# compact.net
KiCad netlist of a schematic drawn in EAGLE
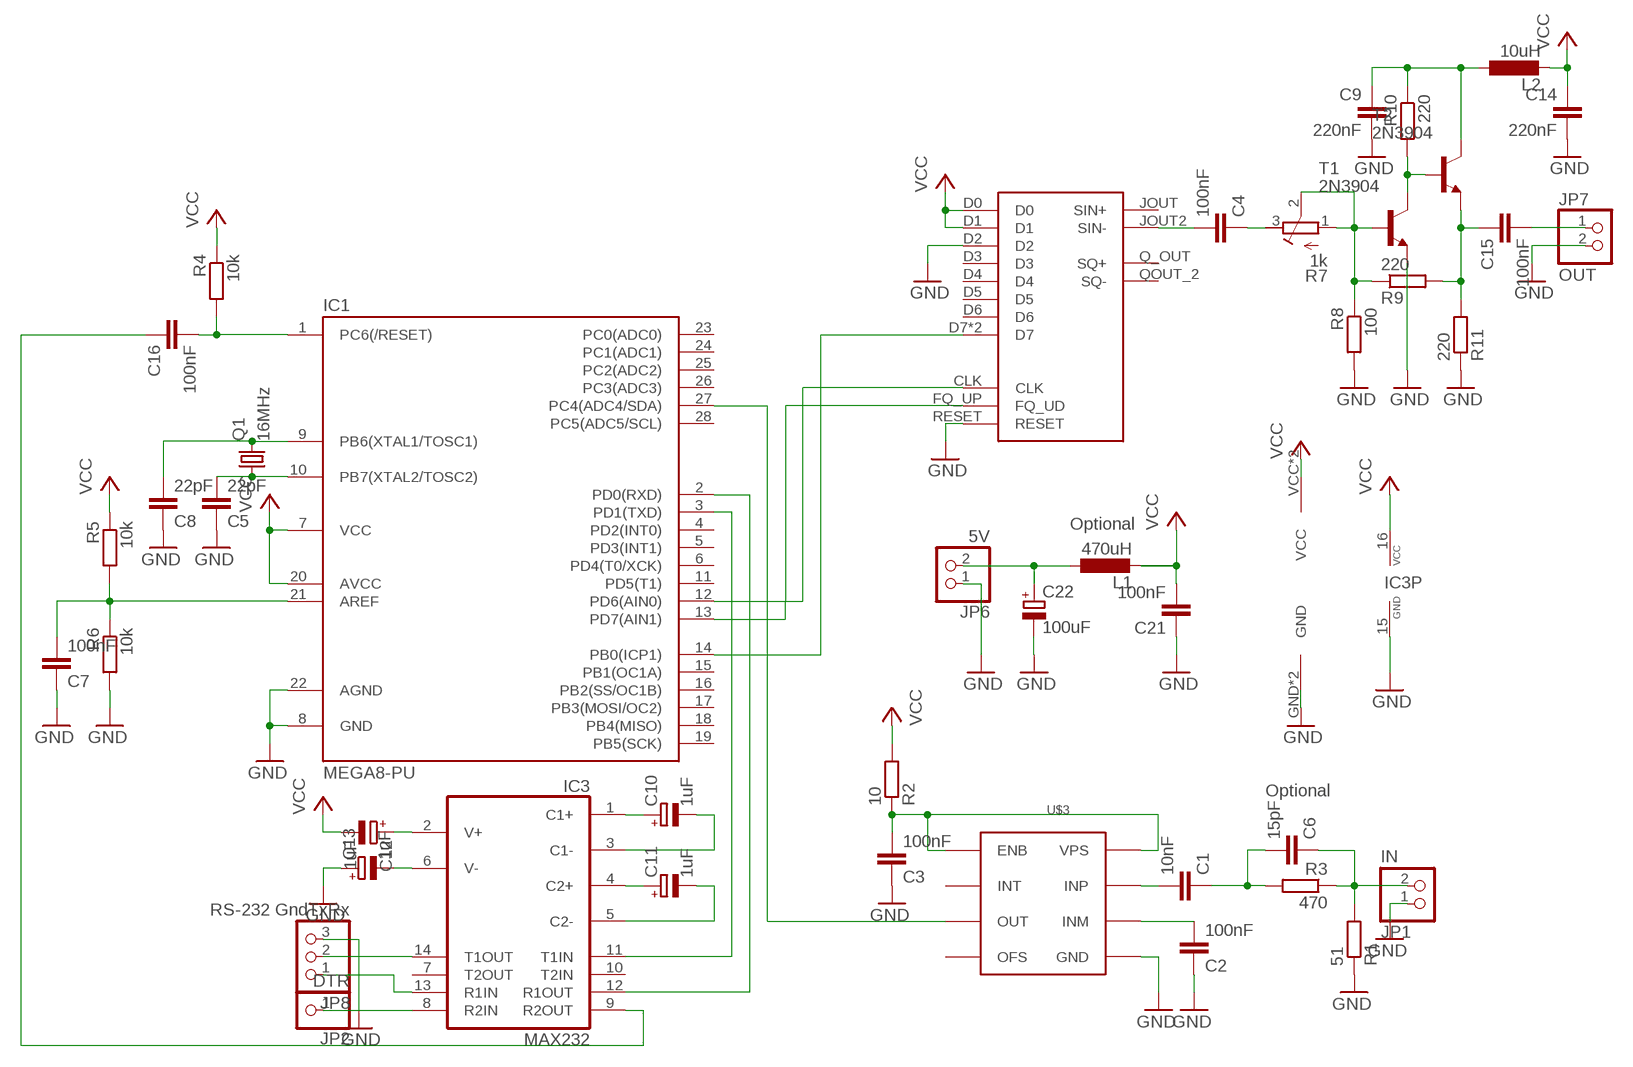
[diagram p0: schematic, sheet 1]

(export (version "E")
  (design (tool "Eeschema 10.0.6"))
  (components
    (comp (ref "C1")
      (value "10nF")
      (footprint "eagle-import:C050-025X075")
      (libsource (lib "eagle-import") (part "C-EU050-025X075"))
    )
    (comp (ref "C2")
      (value "100nF")
      (footprint "eagle-import:C025-025X050")
      (libsource (lib "eagle-import") (part "C-EU025-025X050"))
    )
    (comp (ref "C3")
      (value "100nF")
      (footprint "eagle-import:C025-025X050")
      (libsource (lib "eagle-import") (part "C-EU025-025X050"))
    )
    (comp (ref "C4")
      (value "100nF")
      (footprint "eagle-import:C025-025X050")
      (libsource (lib "eagle-import") (part "C-EU025-025X050"))
    )
    (comp (ref "C5")
      (value "22pF")
      (footprint "eagle-import:C102-043X133")
      (libsource (lib "eagle-import") (part "C-EU102-043X133"))
    )
    (comp (ref "C6")
      (value "15pF")
      (footprint "eagle-import:C025-025X050")
      (libsource (lib "eagle-import") (part "C-EU025-025X050"))
    )
    (comp (ref "C7")
      (value "100nF")
      (footprint "eagle-import:C025-025X050")
      (libsource (lib "eagle-import") (part "C-EU025-025X050"))
    )
    (comp (ref "C8")
      (value "22pF")
      (footprint "eagle-import:C025-025X050")
      (libsource (lib "eagle-import") (part "C-EU025-025X050"))
    )
    (comp (ref "C9")
      (value "220nF")
      (footprint "eagle-import:C025-025X050")
      (libsource (lib "eagle-import") (part "C-EU025-025X050"))
    )
    (comp (ref "C10")
      (value "1uF")
      (footprint "eagle-import:E2,5-6")
      (libsource (lib "eagle-import") (part "CPOL-EUE2.5-6"))
    )
    (comp (ref "C11")
      (value "1uF")
      (footprint "eagle-import:E2,5-5")
      (libsource (lib "eagle-import") (part "CPOL-EUE2.5-5"))
    )
    (comp (ref "C12")
      (value "1uF")
      (footprint "eagle-import:E2,5-5")
      (libsource (lib "eagle-import") (part "CPOL-EUE2.5-5"))
    )
    (comp (ref "C13")
      (value "1uF")
      (footprint "eagle-import:E5-5")
      (libsource (lib "eagle-import") (part "CPOL-EUE5-5"))
    )
    (comp (ref "C14")
      (value "220nF")
      (footprint "eagle-import:C025-025X050")
      (libsource (lib "eagle-import") (part "C-EU025-025X050"))
    )
    (comp (ref "C15")
      (value "100nF")
      (footprint "eagle-import:C050-025X075")
      (libsource (lib "eagle-import") (part "C-EU050-025X075"))
    )
    (comp (ref "C16")
      (value "100nF")
      (footprint "eagle-import:C075-032X103")
      (libsource (lib "eagle-import") (part "C-EU075-032X103"))
    )
    (comp (ref "C21")
      (value "100nF")
      (footprint "eagle-import:C025-025X050")
      (libsource (lib "eagle-import") (part "C-EU025-025X050"))
    )
    (comp (ref "C22")
      (value "100uF")
      (footprint "eagle-import:E2,5-6")
      (libsource (lib "eagle-import") (part "CPOL-EUE2.5-6"))
    )
    (comp (ref "IC1")
      (value "MEGA8-PU")
      (footprint "eagle-import:DIL28-3")
      (libsource (lib "eagle-import") (part "MEGA8-PU"))
    )
    (comp (ref "IC3")
      (value "MAX232")
      (footprint "eagle-import:DIL16")
      (fields (field (name "MF") "MAXIM") (field (name "MPN") "MAX232ACPE+"))
      (libsource (lib "eagle-import") (part "MAX232"))
    )
    (comp (ref "JP1")
      (value "IN")
      (footprint "eagle-import:1X02")
      (libsource (lib "eagle-import") (part "PINHD-1X2"))
    )
    (comp (ref "JP2")
      (value "DTR")
      (footprint "eagle-import:1X01")
      (libsource (lib "eagle-import") (part "PINHD-1X1"))
    )
    (comp (ref "JP6")
      (value "5V")
      (footprint "eagle-import:1X02")
      (libsource (lib "eagle-import") (part "PINHD-1X2"))
    )
    (comp (ref "JP7")
      (value "OUT")
      (footprint "eagle-import:1X02")
      (libsource (lib "eagle-import") (part "PINHD-1X2"))
    )
    (comp (ref "JP8")
      (value "RS-232 GndTxRx")
      (footprint "eagle-import:1X03")
      (libsource (lib "eagle-import") (part "PINHD-1X3"))
    )
    (comp (ref "L1")
      (value "470uH")
      (footprint "eagle-import:0207_5V")
      (libsource (lib "eagle-import") (part "L-EU0207/5V"))
    )
    (comp (ref "L2")
      (value "10uH")
      (footprint "eagle-import:0204_7")
      (libsource (lib "eagle-import") (part "L-EU0204/7"))
    )
    (comp (ref "Q1")
      (value "16MHz")
      (footprint "eagle-import:HC49U-V")
      (libsource (lib "eagle-import") (part "CRYSTALHC49U-V"))
    )
    (comp (ref "R1")
      (value "51")
      (footprint "eagle-import:0204V")
      (libsource (lib "eagle-import") (part "R-EU_0204/2V"))
    )
    (comp (ref "R2")
      (value "10")
      (footprint "eagle-import:0204_5")
      (libsource (lib "eagle-import") (part "R-EU_0204/5"))
    )
    (comp (ref "R3")
      (value "470")
      (footprint "eagle-import:0204V")
      (libsource (lib "eagle-import") (part "R-EU_0204/2V"))
    )
    (comp (ref "R4")
      (value "10k")
      (footprint "eagle-import:0204_5")
      (libsource (lib "eagle-import") (part "R-EU_0204/5"))
    )
    (comp (ref "R5")
      (value "10k")
      (footprint "eagle-import:0204V")
      (libsource (lib "eagle-import") (part "R-EU_0204/2V"))
    )
    (comp (ref "R6")
      (value "10k")
      (footprint "eagle-import:0204_5")
      (libsource (lib "eagle-import") (part "R-EU_0204/5"))
    )
    (comp (ref "R7")
      (value "1k")
      (footprint "eagle-import:RTRIM74W")
      (libsource (lib "eagle-import") (part "R-TRIMM74W"))
    )
    (comp (ref "R8")
      (value "100")
      (footprint "eagle-import:0204V")
      (libsource (lib "eagle-import") (part "R-EU_0204/2V"))
    )
    (comp (ref "R9")
      (value "220")
      (footprint "eagle-import:0204V")
      (libsource (lib "eagle-import") (part "R-EU_0204/2V"))
    )
    (comp (ref "R10")
      (value "220")
      (footprint "eagle-import:0204V")
      (libsource (lib "eagle-import") (part "R-EU_0204/2V"))
    )
    (comp (ref "R11")
      (value "220")
      (footprint "eagle-import:0204V")
      (libsource (lib "eagle-import") (part "R-EU_0204/2V"))
    )
    (comp (ref "T1")
      (value "2N3904")
      (footprint "eagle-import:TO92-EBC")
      (libsource (lib "eagle-import") (part "-NPN-TO92-EBC2N3904"))
    )
    (comp (ref "T2")
      (value "2N3904")
      (footprint "eagle-import:TO92-EBC")
      (libsource (lib "eagle-import") (part "-NPN-TO92-EBC2N3904"))
    )
    (comp (ref "U$1")
      (value "DDS-1")
      (footprint "eagle-import:DDS-1")
      (libsource (lib "eagle-import") (part "DDS-1"))
    )
    (comp (ref "U$3")
      (value "AD8307")
      (footprint "eagle-import:DIL08")
      (libsource (lib "eagle-import") (part "AD8307"))
    )
  )
  (nets
    (net (code "1") (name "GND") (class "Default")
      (node (ref "C13") (pin "+") (pinfunction "+_+") (pintype "passive"))
      (node (ref "C14") (pin "2") (pinfunction "2_2") (pintype "passive"))
      (node (ref "C2") (pin "1") (pinfunction "1_1") (pintype "passive"))
      (node (ref "C21") (pin "1") (pinfunction "1_1") (pintype "passive"))
      (node (ref "C22") (pin "-") (pinfunction "-_-") (pintype "passive"))
      (node (ref "C3") (pin "1") (pinfunction "1_1") (pintype "passive"))
      (node (ref "C5") (pin "1") (pinfunction "1_1") (pintype "passive"))
      (node (ref "C7") (pin "1") (pinfunction "1_1") (pintype "passive"))
      (node (ref "C8") (pin "1") (pinfunction "1_1") (pintype "passive"))
      (node (ref "C9") (pin "2") (pinfunction "2_2") (pintype "passive"))
      (node (ref "IC1") (pin "22") (pinfunction "AGND_22") (pintype "power_in"))
      (node (ref "IC1") (pin "8") (pinfunction "GND_8") (pintype "power_in"))
      (node (ref "IC3") (pin "15") (pinfunction "GND_15") (pintype "power_in"))
      (node (ref "JP1") (pin "1") (pinfunction "1_1") (pintype "passive"))
      (node (ref "JP6") (pin "1") (pinfunction "1_1") (pintype "passive"))
      (node (ref "JP7") (pin "2") (pinfunction "2_2") (pintype "passive"))
      (node (ref "JP8") (pin "3") (pinfunction "3_3") (pintype "passive"))
      (node (ref "R1") (pin "1") (pinfunction "1_1") (pintype "passive"))
      (node (ref "R11") (pin "1") (pinfunction "1_1") (pintype "passive"))
      (node (ref "R6") (pin "2") (pinfunction "2_2") (pintype "passive"))
      (node (ref "R8") (pin "2") (pinfunction "2_2") (pintype "passive"))
      (node (ref "T1") (pin "E") (pinfunction "E_E") (pintype "passive"))
      (node (ref "U$1") (pin "D2") (pinfunction "D2_D2") (pintype "bidirectional"))
      (node (ref "U$1") (pin "GND") (pinfunction "GND_GND") (pintype "bidirectional"))
      (node (ref "U$1") (pin "GND2") (pinfunction "GND_GND2") (pintype "bidirectional"))
      (node (ref "U$1") (pin "RESET") (pinfunction "RESET_RESET") (pintype "bidirectional"))
      (node (ref "U$3") (pin "2") (pinfunction "GND_2") (pintype "bidirectional"))
    )
    (net (code "2") (name "Net-(C1-Pad1)") (class "Default")
      (node (ref "C1") (pin "1") (pinfunction "1_1") (pintype "passive"))
      (node (ref "C6") (pin "2") (pinfunction "2_2") (pintype "passive"))
      (node (ref "R3") (pin "2") (pinfunction "2_2") (pintype "passive"))
    )
    (net (code "3") (name "Net-(C6-Pad1)") (class "Default")
      (node (ref "C6") (pin "1") (pinfunction "1_1") (pintype "passive"))
      (node (ref "JP1") (pin "2") (pinfunction "2_2") (pintype "passive"))
      (node (ref "R1") (pin "2") (pinfunction "2_2") (pintype "passive"))
      (node (ref "R3") (pin "1") (pinfunction "1_1") (pintype "passive"))
    )
    (net (code "4") (name "Net-(C9-Pad1)") (class "Default")
      (node (ref "C9") (pin "1") (pinfunction "1_1") (pintype "passive"))
      (node (ref "L2") (pin "1") (pinfunction "1_1") (pintype "passive"))
      (node (ref "R10") (pin "1") (pinfunction "1_1") (pintype "passive"))
      (node (ref "T2") (pin "C") (pinfunction "C_C") (pintype "passive"))
    )
    (net (code "5") (name "Net-(C15-Pad1)") (class "Default")
      (node (ref "C15") (pin "1") (pinfunction "1_1") (pintype "passive"))
      (node (ref "R11") (pin "2") (pinfunction "2_2") (pintype "passive"))
      (node (ref "R9") (pin "2") (pinfunction "2_2") (pintype "passive"))
      (node (ref "T2") (pin "E") (pinfunction "E_E") (pintype "passive"))
    )
    (net (code "6") (name "Net-(C15-Pad2)") (class "Default")
      (node (ref "C15") (pin "2") (pinfunction "2_2") (pintype "passive"))
      (node (ref "JP7") (pin "1") (pinfunction "1_1") (pintype "passive"))
    )
    (net (code "7") (name "Net-(C22-Pad+)") (class "Default")
      (node (ref "C22") (pin "+") (pinfunction "+_+") (pintype "passive"))
      (node (ref "JP6") (pin "2") (pinfunction "2_2") (pintype "passive"))
      (node (ref "L1") (pin "1") (pinfunction "1_1") (pintype "passive"))
    )
    (net (code "8") (name "Net-(IC1-AREF)") (class "Default")
      (node (ref "C7") (pin "2") (pinfunction "2_2") (pintype "passive"))
      (node (ref "IC1") (pin "21") (pinfunction "AREF_21") (pintype "passive"))
      (node (ref "R5") (pin "2") (pinfunction "2_2") (pintype "passive"))
      (node (ref "R6") (pin "1") (pinfunction "1_1") (pintype "passive"))
    )
    (net (code "9") (name "Net-(IC1-PB0(ICP1))") (class "Default")
      (node (ref "IC1") (pin "14") (pinfunction "PB0(ICP1)_14") (pintype "bidirectional"))
      (node (ref "U$1") (pin "D7") (pinfunction "D7_D7") (pintype "bidirectional"))
      (node (ref "U$1") (pin "D7_2") (pinfunction "D7_D7_2") (pintype "bidirectional"))
    )
    (net (code "10") (name "Net-(IC1-PB6(XTAL1{slash}TOSC1))") (class "Default")
      (node (ref "C8") (pin "2") (pinfunction "2_2") (pintype "passive"))
      (node (ref "IC1") (pin "9") (pinfunction "PB6(XTAL1/TOSC1)_9") (pintype "bidirectional"))
      (node (ref "Q1") (pin "2") (pinfunction "2_2") (pintype "passive"))
    )
    (net (code "11") (name "Net-(IC1-PB7(XTAL2{slash}TOSC2))") (class "Default")
      (node (ref "C5") (pin "2") (pinfunction "2_2") (pintype "passive"))
      (node (ref "IC1") (pin "10") (pinfunction "PB7(XTAL2/TOSC2)_10") (pintype "bidirectional"))
      (node (ref "Q1") (pin "1") (pinfunction "1_1") (pintype "passive"))
    )
    (net (code "12") (name "Net-(IC1-PC4(ADC4{slash}SDA))") (class "Default")
      (node (ref "IC1") (pin "27") (pinfunction "PC4(ADC4/SDA)_27") (pintype "bidirectional"))
      (node (ref "U$3") (pin "4") (pinfunction "OUT_4") (pintype "bidirectional"))
    )
    (net (code "13") (name "Net-(IC1-PC6({slash}RESET))") (class "Default")
      (node (ref "C16") (pin "2") (pinfunction "2_2") (pintype "passive"))
      (node (ref "IC1") (pin "1") (pinfunction "PC6(/RESET)_1") (pintype "bidirectional"))
      (node (ref "R4") (pin "2") (pinfunction "2_2") (pintype "passive"))
    )
    (net (code "14") (name "Net-(IC1-PD0(RXD))") (class "Default")
      (node (ref "IC1") (pin "2") (pinfunction "PD0(RXD)_2") (pintype "bidirectional"))
      (node (ref "IC3") (pin "12") (pinfunction "R1OUT_12") (pintype "output"))
    )
    (net (code "15") (name "Net-(IC1-PD1(TXD))") (class "Default")
      (node (ref "IC1") (pin "3") (pinfunction "PD1(TXD)_3") (pintype "bidirectional"))
      (node (ref "IC3") (pin "11") (pinfunction "T1IN_11") (pintype "input"))
    )
    (net (code "16") (name "Net-(IC1-PD6(AIN0))") (class "Default")
      (node (ref "IC1") (pin "12") (pinfunction "PD6(AIN0)_12") (pintype "bidirectional"))
      (node (ref "U$1") (pin "CLK") (pinfunction "CLK_CLK") (pintype "bidirectional"))
    )
    (net (code "17") (name "Net-(IC1-PD7(AIN1))") (class "Default")
      (node (ref "IC1") (pin "13") (pinfunction "PD7(AIN1)_13") (pintype "bidirectional"))
      (node (ref "U$1") (pin "FQ_UP") (pinfunction "FQ_UD_FQ_UP") (pintype "bidirectional"))
    )
    (net (code "18") (name "Net-(IC3A-C1+)") (class "Default")
      (node (ref "C10") (pin "+") (pinfunction "+_+") (pintype "passive"))
      (node (ref "IC3") (pin "1") (pinfunction "C1+_1") (pintype "bidirectional"))
    )
    (net (code "19") (name "Net-(IC3A-C1-)") (class "Default")
      (node (ref "C10") (pin "-") (pinfunction "-_-") (pintype "passive"))
      (node (ref "IC3") (pin "3") (pinfunction "C1-_3") (pintype "bidirectional"))
    )
    (net (code "20") (name "Net-(IC3A-C2+)") (class "Default")
      (node (ref "C11") (pin "+") (pinfunction "+_+") (pintype "passive"))
      (node (ref "IC3") (pin "4") (pinfunction "C2+_4") (pintype "bidirectional"))
    )
    (net (code "21") (name "Net-(IC3A-C2-)") (class "Default")
      (node (ref "C11") (pin "-") (pinfunction "-_-") (pintype "passive"))
      (node (ref "IC3") (pin "5") (pinfunction "C2-_5") (pintype "bidirectional"))
    )
    (net (code "22") (name "Net-(IC3A-R1IN)") (class "Default")
      (node (ref "IC3") (pin "13") (pinfunction "R1IN_13") (pintype "input"))
      (node (ref "JP8") (pin "1") (pinfunction "1_1") (pintype "passive"))
    )
    (net (code "23") (name "Net-(IC3A-R2IN)") (class "Default")
      (node (ref "IC3") (pin "8") (pinfunction "R2IN_8") (pintype "input"))
      (node (ref "JP2") (pin "1") (pinfunction "1_1") (pintype "passive"))
    )
    (net (code "24") (name "Net-(IC3A-R2OUT)") (class "Default")
      (node (ref "C16") (pin "1") (pinfunction "1_1") (pintype "passive"))
      (node (ref "IC3") (pin "9") (pinfunction "R2OUT_9") (pintype "output"))
    )
    (net (code "25") (name "Net-(IC3A-T1OUT)") (class "Default")
      (node (ref "IC3") (pin "14") (pinfunction "T1OUT_14") (pintype "output"))
      (node (ref "JP8") (pin "2") (pinfunction "2_2") (pintype "passive"))
    )
    (net (code "26") (name "Net-(IC3A-V+)") (class "Default")
      (node (ref "C12") (pin "+") (pinfunction "+_+") (pintype "passive"))
      (node (ref "IC3") (pin "2") (pinfunction "V+_2") (pintype "bidirectional"))
    )
    (net (code "27") (name "Net-(IC3A-V-)") (class "Default")
      (node (ref "C13") (pin "-") (pinfunction "-_-") (pintype "passive"))
      (node (ref "IC3") (pin "6") (pinfunction "V-_6") (pintype "bidirectional"))
    )
    (net (code "28") (name "Net-(R7-A)") (class "Default")
      (node (ref "C4") (pin "1") (pinfunction "1_1") (pintype "passive"))
      (node (ref "R7") (pin "3") (pinfunction "A_3") (pintype "passive"))
    )
    (net (code "29") (name "Net-(R7-E)") (class "Default")
      (node (ref "R7") (pin "1") (pinfunction "E_1") (pintype "passive"))
      (node (ref "R7") (pin "2") (pinfunction "S_2") (pintype "passive"))
      (node (ref "R8") (pin "1") (pinfunction "1_1") (pintype "passive"))
      (node (ref "R9") (pin "1") (pinfunction "1_1") (pintype "passive"))
      (node (ref "T1") (pin "B") (pinfunction "B_B") (pintype "passive"))
    )
    (net (code "30") (name "Net-(R10-Pad2)") (class "Default")
      (node (ref "R10") (pin "2") (pinfunction "2_2") (pintype "passive"))
      (node (ref "T1") (pin "C") (pinfunction "C_C") (pintype "passive"))
      (node (ref "T2") (pin "B") (pinfunction "B_B") (pintype "passive"))
    )
    (net (code "31") (name "Net-(U$1A-SIN-)") (class "Default")
      (node (ref "C4") (pin "2") (pinfunction "2_2") (pintype "passive"))
      (node (ref "U$1") (pin "JOUT2") (pinfunction "SIN-_JOUT2") (pintype "bidirectional"))
    )
    (net (code "32") (name "Net-(U$3-ENB)") (class "Default")
      (node (ref "C3") (pin "2") (pinfunction "2_2") (pintype "passive"))
      (node (ref "R2") (pin "1") (pinfunction "1_1") (pintype "passive"))
      (node (ref "U$3") (pin "6") (pinfunction "ENB_6") (pintype "bidirectional"))
      (node (ref "U$3") (pin "7") (pinfunction "VPS_7") (pintype "bidirectional"))
    )
    (net (code "33") (name "Net-(U$3-INM)") (class "Default")
      (node (ref "C2") (pin "2") (pinfunction "2_2") (pintype "passive"))
      (node (ref "U$3") (pin "1") (pinfunction "INM_1") (pintype "bidirectional"))
    )
    (net (code "34") (name "Net-(U$3-INP)") (class "Default")
      (node (ref "C1") (pin "2") (pinfunction "2_2") (pintype "passive"))
      (node (ref "U$3") (pin "8") (pinfunction "INP_8") (pintype "bidirectional"))
    )
    (net (code "35") (name "VCC") (class "Default")
      (node (ref "C12") (pin "-") (pinfunction "-_-") (pintype "passive"))
      (node (ref "C14") (pin "1") (pinfunction "1_1") (pintype "passive"))
      (node (ref "C21") (pin "2") (pinfunction "2_2") (pintype "passive"))
      (node (ref "IC1") (pin "20") (pinfunction "AVCC_20") (pintype "passive"))
      (node (ref "IC1") (pin "7") (pinfunction "VCC_7") (pintype "power_in"))
      (node (ref "IC3") (pin "16") (pinfunction "VCC_16") (pintype "power_in"))
      (node (ref "L1") (pin "2") (pinfunction "2_2") (pintype "passive"))
      (node (ref "L2") (pin "2") (pinfunction "2_2") (pintype "passive"))
      (node (ref "R2") (pin "2") (pinfunction "2_2") (pintype "passive"))
      (node (ref "R4") (pin "1") (pinfunction "1_1") (pintype "passive"))
      (node (ref "R5") (pin "1") (pinfunction "1_1") (pintype "passive"))
      (node (ref "U$1") (pin "D0") (pinfunction "D0_D0") (pintype "bidirectional"))
      (node (ref "U$1") (pin "D1") (pinfunction "D1_D1") (pintype "bidirectional"))
      (node (ref "U$1") (pin "VCC") (pinfunction "VCC_VCC") (pintype "bidirectional"))
      (node (ref "U$1") (pin "VCC2") (pinfunction "VCC_VCC2") (pintype "bidirectional"))
    )
    (net (code "36") (name "unconnected-(IC1-PB1(OC1A)-Pad15)") (class "Default")
      (node (ref "IC1") (pin "15") (pinfunction "PB1(OC1A)_15") (pintype "bidirectional"))
    )
    (net (code "37") (name "unconnected-(IC1-PB2(SS{slash}OC1B)-Pad16)") (class "Default")
      (node (ref "IC1") (pin "16") (pinfunction "PB2(SS/OC1B)_16") (pintype "bidirectional"))
    )
    (net (code "38") (name "unconnected-(IC1-PB3(MOSI{slash}OC2)-Pad17)") (class "Default")
      (node (ref "IC1") (pin "17") (pinfunction "PB3(MOSI/OC2)_17") (pintype "bidirectional"))
    )
    (net (code "39") (name "unconnected-(IC1-PB4(MISO)-Pad18)") (class "Default")
      (node (ref "IC1") (pin "18") (pinfunction "PB4(MISO)_18") (pintype "bidirectional"))
    )
    (net (code "40") (name "unconnected-(IC1-PB5(SCK)-Pad19)") (class "Default")
      (node (ref "IC1") (pin "19") (pinfunction "PB5(SCK)_19") (pintype "bidirectional"))
    )
    (net (code "41") (name "unconnected-(IC1-PC0(ADC0)-Pad23)") (class "Default")
      (node (ref "IC1") (pin "23") (pinfunction "PC0(ADC0)_23") (pintype "bidirectional"))
    )
    (net (code "42") (name "unconnected-(IC1-PC1(ADC1)-Pad24)") (class "Default")
      (node (ref "IC1") (pin "24") (pinfunction "PC1(ADC1)_24") (pintype "bidirectional"))
    )
    (net (code "43") (name "unconnected-(IC1-PC2(ADC2)-Pad25)") (class "Default")
      (node (ref "IC1") (pin "25") (pinfunction "PC2(ADC2)_25") (pintype "bidirectional"))
    )
    (net (code "44") (name "unconnected-(IC1-PC3(ADC3)-Pad26)") (class "Default")
      (node (ref "IC1") (pin "26") (pinfunction "PC3(ADC3)_26") (pintype "bidirectional"))
    )
    (net (code "45") (name "unconnected-(IC1-PC5(ADC5{slash}SCL)-Pad28)") (class "Default")
      (node (ref "IC1") (pin "28") (pinfunction "PC5(ADC5/SCL)_28") (pintype "bidirectional"))
    )
    (net (code "46") (name "unconnected-(IC1-PD2(INT0)-Pad4)") (class "Default")
      (node (ref "IC1") (pin "4") (pinfunction "PD2(INT0)_4") (pintype "bidirectional"))
    )
    (net (code "47") (name "unconnected-(IC1-PD3(INT1)-Pad5)") (class "Default")
      (node (ref "IC1") (pin "5") (pinfunction "PD3(INT1)_5") (pintype "bidirectional"))
    )
    (net (code "48") (name "unconnected-(IC1-PD4(T0{slash}XCK)-Pad6)") (class "Default")
      (node (ref "IC1") (pin "6") (pinfunction "PD4(T0/XCK)_6") (pintype "bidirectional"))
    )
    (net (code "49") (name "unconnected-(IC1-PD5(T1)-Pad11)") (class "Default")
      (node (ref "IC1") (pin "11") (pinfunction "PD5(T1)_11") (pintype "bidirectional"))
    )
    (net (code "50") (name "unconnected-(IC3A-T2IN-Pad10)") (class "Default")
      (node (ref "IC3") (pin "10") (pinfunction "T2IN_10") (pintype "input"))
    )
    (net (code "51") (name "unconnected-(IC3A-T2OUT-Pad7)") (class "Default")
      (node (ref "IC3") (pin "7") (pinfunction "T2OUT_7") (pintype "output"))
    )
    (net (code "52") (name "unconnected-(U$1-PadD3)") (class "Default")
      (node (ref "U$1") (pin "D3") (pinfunction "D3_D3") (pintype "bidirectional"))
    )
    (net (code "53") (name "unconnected-(U$1-PadD4)") (class "Default")
      (node (ref "U$1") (pin "D4") (pinfunction "D4_D4") (pintype "bidirectional"))
    )
    (net (code "54") (name "unconnected-(U$1-PadD5)") (class "Default")
      (node (ref "U$1") (pin "D5") (pinfunction "D5_D5") (pintype "bidirectional"))
    )
    (net (code "55") (name "unconnected-(U$1-PadD6)") (class "Default")
      (node (ref "U$1") (pin "D6") (pinfunction "D6_D6") (pintype "bidirectional"))
    )
    (net (code "56") (name "unconnected-(U$1A-SIN+-PadJOUT)") (class "Default")
      (node (ref "U$1") (pin "JOUT") (pinfunction "SIN+_JOUT") (pintype "bidirectional"))
    )
    (net (code "57") (name "unconnected-(U$1A-SQ+-PadQ_OUT)") (class "Default")
      (node (ref "U$1") (pin "Q_OUT") (pinfunction "SQ+_Q_OUT") (pintype "bidirectional"))
    )
    (net (code "58") (name "unconnected-(U$1A-SQ--PadQOUT_2)") (class "Default")
      (node (ref "U$1") (pin "QOUT_2") (pinfunction "SQ-_QOUT_2") (pintype "bidirectional"))
    )
    (net (code "59") (name "unconnected-(U$3-INT-Pad5)") (class "Default")
      (node (ref "U$3") (pin "5") (pinfunction "INT_5") (pintype "bidirectional"))
    )
    (net (code "60") (name "unconnected-(U$3-OFS-Pad3)") (class "Default")
      (node (ref "U$3") (pin "3") (pinfunction "OFS_3") (pintype "bidirectional"))
    )
  )
)
